# Urukul_FPGA.net
KiCad netlist of a schematic drawn in Altium Designer
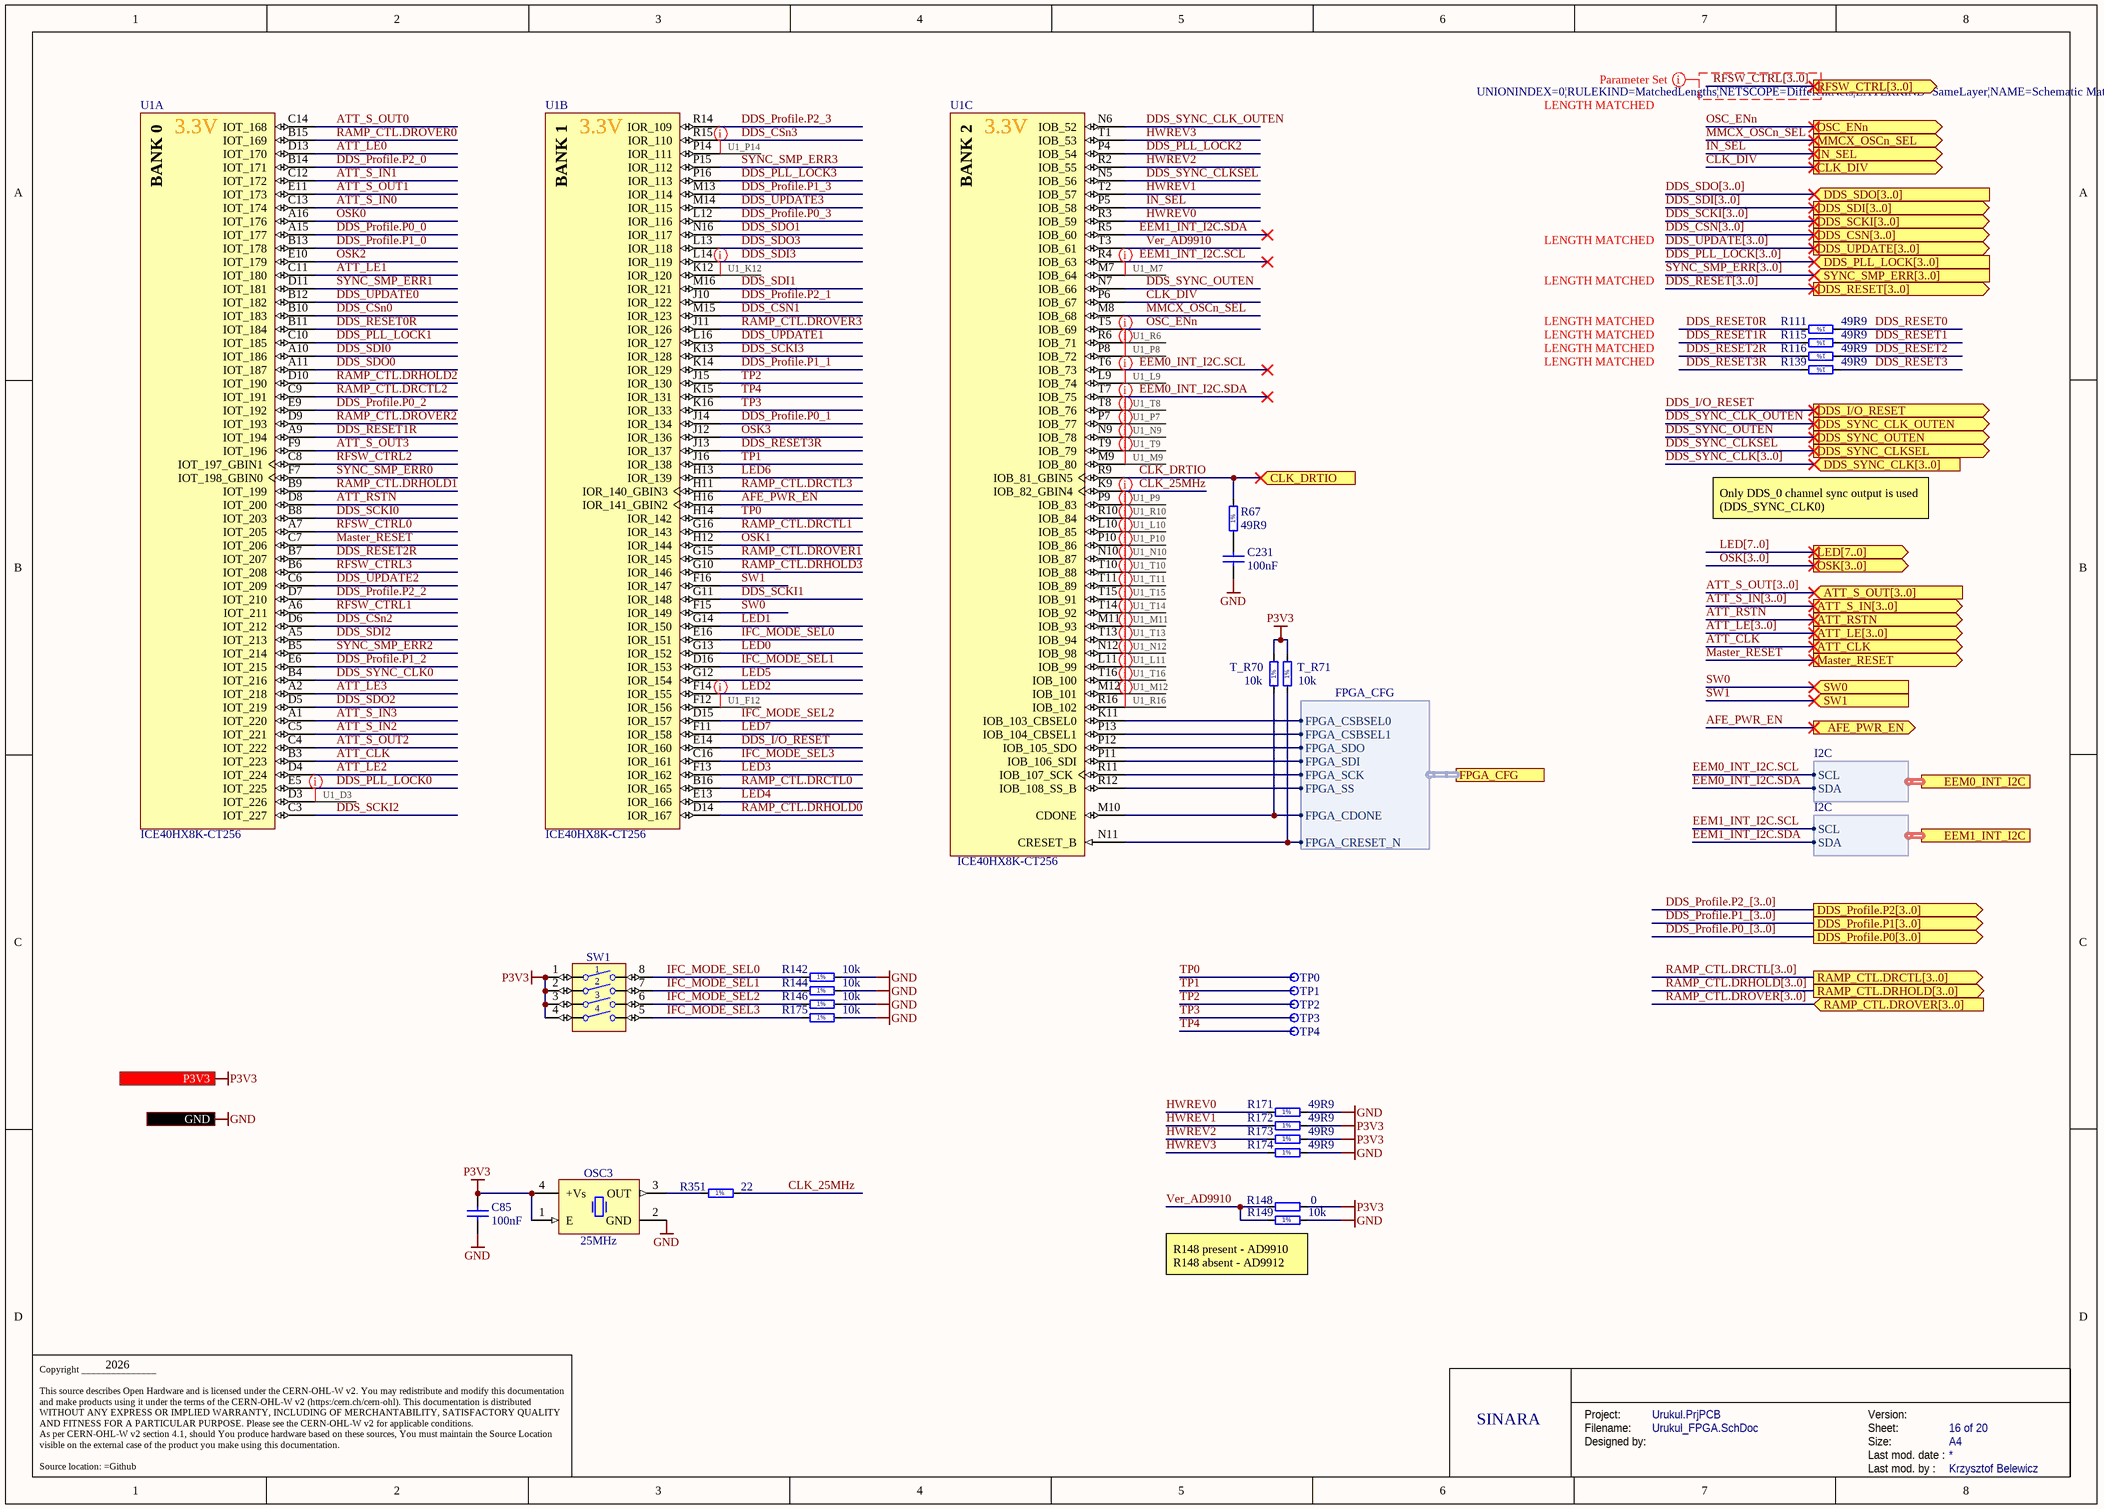
[diagram p0: Urukul_FPGA.SchDoc]

(export (version "E")
  (design (tool "Eeschema 10.0.6"))
  (components
    (comp (ref "C85")
      (value "100nF")
      (footprint "CAPC1005X55N")
      (description "Non-polarised capacitor")
      (fields
        (field (name "PART NUMBER") "CC0402_100NF_16V_10%_X5R")
        (field (name "VOLTAGE") "16V")
        (field (name "AUTHOR") "CERN DEM JLC")
      )
      (libsource (lib "Capacitors") (part "Capacitor - non polarized"))
    )
    (comp (ref "C231")
      (value "100nF")
      (footprint "CAPC1005X55N")
      (description "Non-polarised capacitor")
      (fields
        (field (name "PART NUMBER") "CC0402_100NF_16V_10%_X5R")
        (field (name "VOLTAGE") "16V")
        (field (name "AUTHOR") "CERN DEM JLC")
      )
      (libsource (lib "Capacitors") (part "Capacitor - non polarized"))
    )
    (comp (ref "OSC3")
      (value "25MHz")
      (footprint "OSC_IQD_CFPS-39")
      (description "Oscillator 4 pins 1=E 2=GND 3=OUT 4=+Vs")
      (fields
        (field (name "PART NUMBER") "OSC_25MHZ_IQD_LFSPXO025165")
        (field (name "MANUFACTURER") "IQD FREQUENCY PRODUCTS")
        (field (name "AUTHOR") "CERN DEM JLC")
      )
      (libsource (lib "ICs And Semiconductors") (part "Oscillator 1E 2GND 3OUT 4Vs"))
    )
    (comp (ref "R67")
      (value "49R9")
      (footprint "RESC1005X40N")
      (description "Resistor - 1%")
      (fields
        (field (name "PART NUMBER") "R0402_49R9_1%_0.0625W_100PPM")
        (field (name "POWER") "0.0625W")
        (field (name "AUTHOR") "CERN DEM JLC")
      )
      (libsource (lib "Resistors") (part "Resistor - 1%"))
    )
    (comp (ref "R111")
      (value "49R9")
      (footprint "RESC1005X40N")
      (description "Resistor - 1%")
      (fields
        (field (name "PART NUMBER") "R0402_49R9_1%_0.0625W_100PPM")
        (field (name "POWER") "0.0625W")
        (field (name "AUTHOR") "CERN DEM JLC")
      )
      (libsource (lib "Resistors") (part "Resistor - 1%"))
    )
    (comp (ref "R115")
      (value "49R9")
      (footprint "RESC1005X40N")
      (description "Resistor - 1%")
      (fields
        (field (name "PART NUMBER") "R0402_49R9_1%_0.0625W_100PPM")
        (field (name "POWER") "0.0625W")
        (field (name "AUTHOR") "CERN DEM JLC")
      )
      (libsource (lib "Resistors") (part "Resistor - 1%"))
    )
    (comp (ref "R116")
      (value "49R9")
      (footprint "RESC1005X40N")
      (description "Resistor - 1%")
      (fields
        (field (name "PART NUMBER") "R0402_49R9_1%_0.0625W_100PPM")
        (field (name "POWER") "0.0625W")
        (field (name "AUTHOR") "CERN DEM JLC")
      )
      (libsource (lib "Resistors") (part "Resistor - 1%"))
    )
    (comp (ref "R139")
      (value "49R9")
      (footprint "RESC1005X40N")
      (description "Resistor - 1%")
      (fields
        (field (name "PART NUMBER") "R0402_49R9_1%_0.0625W_100PPM")
        (field (name "POWER") "0.0625W")
        (field (name "AUTHOR") "CERN DEM JLC")
      )
      (libsource (lib "Resistors") (part "Resistor - 1%"))
    )
    (comp (ref "R142")
      (value "10k")
      (footprint "RESC1005X40N")
      (description "Resistor - 1%")
      (fields
        (field (name "PART NUMBER") "R0402_10K_1%_0.0625W_100PPM")
        (field (name "POWER") "0.0625W")
        (field (name "AUTHOR") "CERN DEM JLC")
      )
      (libsource (lib "Resistors") (part "Resistor - 1%"))
    )
    (comp (ref "R144")
      (value "10k")
      (footprint "RESC1005X40N")
      (description "Resistor - 1%")
      (fields
        (field (name "PART NUMBER") "R0402_10K_1%_0.0625W_100PPM")
        (field (name "POWER") "0.0625W")
        (field (name "AUTHOR") "CERN DEM JLC")
      )
      (libsource (lib "Resistors") (part "Resistor - 1%"))
    )
    (comp (ref "R146")
      (value "10k")
      (footprint "RESC1005X40N")
      (description "Resistor - 1%")
      (fields
        (field (name "PART NUMBER") "R0402_10K_1%_0.0625W_100PPM")
        (field (name "POWER") "0.0625W")
        (field (name "AUTHOR") "CERN DEM JLC")
      )
      (libsource (lib "Resistors") (part "Resistor - 1%"))
    )
    (comp (ref "R148")
      (value "0")
      (footprint "RESC1005X40N")
      (description "Resistor")
      (fields
        (field (name "PART NUMBER") "R0402_0R_JUMPER")
        (field (name "MANUFACTURER") "GENERIC")
        (field (name "AUTHOR") "CERN DEM JLC")
      )
      (libsource (lib "Resistors") (part "Resistor"))
    )
    (comp (ref "R149")
      (value "10k")
      (footprint "RESC1005X40N")
      (description "Resistor - 1%")
      (fields
        (field (name "PART NUMBER") "R0402_10K_1%_0.0625W_100PPM")
        (field (name "POWER") "0.0625W")
        (field (name "AUTHOR") "CERN DEM JLC")
      )
      (libsource (lib "Resistors") (part "Resistor - 1%"))
    )
    (comp (ref "R171")
      (value "49R9")
      (footprint "RESC1005X40N")
      (description "Resistor - 1%")
      (fields
        (field (name "PART NUMBER") "R0402_49R9_1%_0.0625W_100PPM")
        (field (name "POWER") "0.0625W")
        (field (name "AUTHOR") "CERN DEM JLC")
      )
      (libsource (lib "Resistors") (part "Resistor - 1%"))
    )
    (comp (ref "R172")
      (value "49R9")
      (footprint "RESC1005X40N")
      (description "Resistor - 1%")
      (fields
        (field (name "PART NUMBER") "R0402_49R9_1%_0.0625W_100PPM")
        (field (name "POWER") "0.0625W")
        (field (name "AUTHOR") "CERN DEM JLC")
      )
      (libsource (lib "Resistors") (part "Resistor - 1%"))
    )
    (comp (ref "R173")
      (value "49R9")
      (footprint "RESC1005X40N")
      (description "Resistor - 1%")
      (fields
        (field (name "PART NUMBER") "R0402_49R9_1%_0.0625W_100PPM")
        (field (name "POWER") "0.0625W")
        (field (name "AUTHOR") "CERN DEM JLC")
      )
      (libsource (lib "Resistors") (part "Resistor - 1%"))
    )
    (comp (ref "R174")
      (value "49R9")
      (footprint "RESC1005X40N")
      (description "Resistor - 1%")
      (fields
        (field (name "PART NUMBER") "R0402_49R9_1%_0.0625W_100PPM")
        (field (name "POWER") "0.0625W")
        (field (name "AUTHOR") "CERN DEM JLC")
      )
      (libsource (lib "Resistors") (part "Resistor - 1%"))
    )
    (comp (ref "R175")
      (value "10k")
      (footprint "RESC1005X40N")
      (description "Resistor - 1%")
      (fields
        (field (name "PART NUMBER") "R0402_10K_1%_0.0625W_100PPM")
        (field (name "POWER") "0.0625W")
        (field (name "AUTHOR") "CERN DEM JLC")
      )
      (libsource (lib "Resistors") (part "Resistor - 1%"))
    )
    (comp (ref "R351")
      (value "22")
      (footprint "RESC1005X40N")
      (description "Resistor - 1%")
      (fields
        (field (name "PART NUMBER") "R0402_22R_1%_0.0625W_100PPM")
        (field (name "POWER") "0.0625W")
        (field (name "AUTHOR") "CERN DEM JLC")
      )
      (libsource (lib "Resistors") (part "Resistor - 1%"))
    )
    (comp (ref "SW1")
      (value "Switch")
      (footprint "SW_TYCO_1571983-4")
      (description "4 Ways SPST DIP Switch")
      (fields
        (field (name "PART NUMBER") "SW_TYCO_1571983-4")
        (field (name "MANUFACTURER") "TYCO")
        (field (name "AUTHOR") "CERN DEM JLC")
      )
      (libsource (lib "Eletro-mechanical") (part "SW 4x SPST DIP Switch"))
    )
    (comp (ref "TP0")
      (value "Test Point")
      (footprint "TPS127")
      (fields (field (name "PART NUMBER") "SMD_PAD_1.27X1.27MM") (field (name "AUTHOR") "CERN DEM JLC"))
      (libsource (lib "Eletro-mechanical") (part "Test Point"))
    )
    (comp (ref "TP1")
      (value "Test Point")
      (footprint "TPS127")
      (fields (field (name "PART NUMBER") "SMD_PAD_1.27X1.27MM") (field (name "AUTHOR") "CERN DEM JLC"))
      (libsource (lib "Eletro-mechanical") (part "Test Point"))
    )
    (comp (ref "TP2")
      (value "Test Point")
      (footprint "TPS127")
      (fields (field (name "PART NUMBER") "SMD_PAD_1.27X1.27MM") (field (name "AUTHOR") "CERN DEM JLC"))
      (libsource (lib "Eletro-mechanical") (part "Test Point"))
    )
    (comp (ref "TP3")
      (value "Test Point")
      (footprint "TPS127")
      (fields (field (name "PART NUMBER") "SMD_PAD_1.27X1.27MM") (field (name "AUTHOR") "CERN DEM JLC"))
      (libsource (lib "Eletro-mechanical") (part "Test Point"))
    )
    (comp (ref "TP4")
      (value "Test Point")
      (footprint "TPS127")
      (fields (field (name "PART NUMBER") "SMD_PAD_1.27X1.27MM") (field (name "AUTHOR") "CERN DEM JLC"))
      (libsource (lib "Eletro-mechanical") (part "Test Point"))
    )
    (comp (ref "T_R70")
      (value "10k")
      (footprint "RESC1005X40N")
      (description "Resistor - 1%")
      (fields
        (field (name "PART NUMBER") "R0402_10K_1%_0.0625W_100PPM")
        (field (name "POWER") "0.0625W")
        (field (name "AUTHOR") "CERN DEM JLC")
      )
      (libsource (lib "Resistors") (part "Resistor - 1%"))
    )
    (comp (ref "T_R71")
      (value "10k")
      (footprint "RESC1005X40N")
      (description "Resistor - 1%")
      (fields
        (field (name "PART NUMBER") "R0402_10K_1%_0.0625W_100PPM")
        (field (name "POWER") "0.0625W")
        (field (name "AUTHOR") "CERN DEM JLC")
      )
      (libsource (lib "Resistors") (part "Resistor - 1%"))
    )
    (comp (ref "U1")
      (value "ICE40HX8K-CT256")
      (footprint "LATC-caBGA-256")
      (fields (field (name "MANUFACTURER") "Lattice Semiconductor"))
      (libsource (lib "Altium Content Vault") (part "LATC-HX8K-caBGA-256"))
    )
  )
  (nets
    (net (code "9") (name "/AFE_PWR_EN") (class "Default")
      (node (ref "U1") (pin "H16") (pinfunction "IOR_141_GBIN2_H16") (pintype "bidirectional+no_connect"))
    )
    (net (code "10") (name "/ATT_CLK") (class "Default")
      (node (ref "U1") (pin "B3") (pinfunction "IOT_223_B3") (pintype "bidirectional+no_connect"))
    )
    (net (code "11") (name "/ATT_LE0") (class "Default")
      (node (ref "U1") (pin "D13") (pinfunction "IOT_170_D13") (pintype "bidirectional"))
    )
    (net (code "12") (name "/ATT_LE1") (class "Default")
      (node (ref "U1") (pin "C11") (pinfunction "IOT_180_C11") (pintype "bidirectional"))
    )
    (net (code "13") (name "/ATT_LE2") (class "Default")
      (node (ref "U1") (pin "D4") (pinfunction "IOT_224_D4") (pintype "bidirectional"))
    )
    (net (code "14") (name "/ATT_LE3") (class "Default")
      (node (ref "U1") (pin "A2") (pinfunction "IOT_218_A2") (pintype "bidirectional"))
    )
    (net (code "16") (name "/ATT_RSTN") (class "Default")
      (node (ref "U1") (pin "D8") (pinfunction "IOT_200_D8") (pintype "bidirectional+no_connect"))
    )
    (net (code "17") (name "/ATT_S_IN0") (class "Default")
      (node (ref "U1") (pin "C13") (pinfunction "IOT_174_C13") (pintype "bidirectional"))
    )
    (net (code "18") (name "/ATT_S_IN1") (class "Default")
      (node (ref "U1") (pin "C12") (pinfunction "IOT_172_C12") (pintype "bidirectional"))
    )
    (net (code "19") (name "/ATT_S_IN2") (class "Default")
      (node (ref "U1") (pin "C5") (pinfunction "IOT_221_C5") (pintype "bidirectional"))
    )
    (net (code "20") (name "/ATT_S_IN3") (class "Default")
      (node (ref "U1") (pin "A1") (pinfunction "IOT_220_A1") (pintype "bidirectional"))
    )
    (net (code "22") (name "/ATT_S_OUT0") (class "Default")
      (node (ref "U1") (pin "C14") (pinfunction "IOT_168_C14") (pintype "bidirectional"))
    )
    (net (code "23") (name "/ATT_S_OUT1") (class "Default")
      (node (ref "U1") (pin "E11") (pinfunction "IOT_173_E11") (pintype "bidirectional"))
    )
    (net (code "24") (name "/ATT_S_OUT2") (class "Default")
      (node (ref "U1") (pin "C4") (pinfunction "IOT_222_C4") (pintype "bidirectional"))
    )
    (net (code "25") (name "/ATT_S_OUT3") (class "Default")
      (node (ref "U1") (pin "F9") (pinfunction "IOT_196_F9") (pintype "bidirectional"))
    )
    (net (code "27") (name "/CLK_25MHz") (class "Default")
      (node (ref "R351") (pin "2") (pinfunction "2_2") (pintype "passive"))
      (node (ref "U1") (pin "K9") (pinfunction "IOB_82_GBIN4_K9") (pintype "bidirectional"))
    )
    (net (code "28") (name "/CLK_DIV") (class "Default")
      (node (ref "U1") (pin "P6") (pinfunction "IOB_67_P6") (pintype "bidirectional"))
    )
    (net (code "29") (name "/CLK_DRTIO") (class "Default")
      (node (ref "R67") (pin "2") (pinfunction "2_2") (pintype "passive"))
      (node (ref "U1") (pin "R9") (pinfunction "IOB_81_GBIN5_R9") (pintype "bidirectional"))
    )
    (net (code "30") (name "/DDS_CSN1") (class "Default")
      (node (ref "U1") (pin "M15") (pinfunction "IOR_123_M15") (pintype "bidirectional"))
    )
    (net (code "32") (name "/DDS_CSn0") (class "Default")
      (node (ref "U1") (pin "B10") (pinfunction "IOT_183_B10") (pintype "bidirectional"))
    )
    (net (code "33") (name "/DDS_CSn2") (class "Default")
      (node (ref "U1") (pin "D6") (pinfunction "IOT_212_D6") (pintype "bidirectional"))
    )
    (net (code "34") (name "/DDS_CSn3") (class "Default")
      (node (ref "U1") (pin "R15") (pinfunction "IOR_110_R15") (pintype "bidirectional"))
    )
    (net (code "35") (name "/DDS_I{slash}O_RESET") (class "Default")
      (node (ref "U1") (pin "E14") (pinfunction "IOR_160_E14") (pintype "bidirectional"))
    )
    (net (code "36") (name "/DDS_PLL_LOCK0") (class "Default")
      (node (ref "U1") (pin "E5") (pinfunction "IOT_225_E5") (pintype "bidirectional"))
    )
    (net (code "37") (name "/DDS_PLL_LOCK1") (class "Default")
      (node (ref "U1") (pin "C10") (pinfunction "IOT_185_C10") (pintype "bidirectional"))
    )
    (net (code "38") (name "/DDS_PLL_LOCK2") (class "Default")
      (node (ref "U1") (pin "P4") (pinfunction "IOB_54_P4") (pintype "bidirectional"))
    )
    (net (code "39") (name "/DDS_PLL_LOCK3") (class "Default")
      (node (ref "U1") (pin "P16") (pinfunction "IOR_113_P16") (pintype "bidirectional"))
    )
    (net (code "41") (name "/DDS_Profile.P0_0") (class "Default")
      (node (ref "U1") (pin "A15") (pinfunction "IOT_177_A15") (pintype "bidirectional"))
    )
    (net (code "42") (name "/DDS_Profile.P0_1") (class "Default")
      (node (ref "U1") (pin "J14") (pinfunction "IOR_134_J14") (pintype "bidirectional"))
    )
    (net (code "43") (name "/DDS_Profile.P0_2") (class "Default")
      (node (ref "U1") (pin "E9") (pinfunction "IOT_192_E9") (pintype "bidirectional"))
    )
    (net (code "44") (name "/DDS_Profile.P0_3") (class "Default")
      (node (ref "U1") (pin "L12") (pinfunction "IOR_116_L12") (pintype "bidirectional"))
    )
    (net (code "46") (name "/DDS_Profile.P1_0") (class "Default")
      (node (ref "U1") (pin "B13") (pinfunction "IOT_178_B13") (pintype "bidirectional"))
    )
    (net (code "47") (name "/DDS_Profile.P1_1") (class "Default")
      (node (ref "U1") (pin "K14") (pinfunction "IOR_129_K14") (pintype "bidirectional"))
    )
    (net (code "48") (name "/DDS_Profile.P1_2") (class "Default")
      (node (ref "U1") (pin "E6") (pinfunction "IOT_215_E6") (pintype "bidirectional"))
    )
    (net (code "49") (name "/DDS_Profile.P1_3") (class "Default")
      (node (ref "U1") (pin "M13") (pinfunction "IOR_114_M13") (pintype "bidirectional"))
    )
    (net (code "51") (name "/DDS_Profile.P2_0") (class "Default")
      (node (ref "U1") (pin "B14") (pinfunction "IOT_171_B14") (pintype "bidirectional"))
    )
    (net (code "52") (name "/DDS_Profile.P2_1") (class "Default")
      (node (ref "U1") (pin "J10") (pinfunction "IOR_122_J10") (pintype "bidirectional"))
    )
    (net (code "53") (name "/DDS_Profile.P2_2") (class "Default")
      (node (ref "U1") (pin "D7") (pinfunction "IOT_210_D7") (pintype "bidirectional"))
    )
    (net (code "54") (name "/DDS_Profile.P2_3") (class "Default")
      (node (ref "U1") (pin "R14") (pinfunction "IOR_109_R14") (pintype "bidirectional"))
    )
    (net (code "56") (name "/DDS_RESET0") (class "Default")
      (node (ref "R111") (pin "1") (pinfunction "1_1") (pintype "passive"))
    )
    (net (code "57") (name "/DDS_RESET0R") (class "Default")
      (node (ref "R111") (pin "2") (pinfunction "2_2") (pintype "passive"))
      (node (ref "U1") (pin "B11") (pinfunction "IOT_184_B11") (pintype "bidirectional"))
    )
    (net (code "58") (name "/DDS_RESET1") (class "Default")
      (node (ref "R115") (pin "1") (pinfunction "1_1") (pintype "passive"))
    )
    (net (code "59") (name "/DDS_RESET1R") (class "Default")
      (node (ref "R115") (pin "2") (pinfunction "2_2") (pintype "passive"))
      (node (ref "U1") (pin "A9") (pinfunction "IOT_194_A9") (pintype "bidirectional"))
    )
    (net (code "60") (name "/DDS_RESET2") (class "Default")
      (node (ref "R116") (pin "1") (pinfunction "1_1") (pintype "passive"))
    )
    (net (code "61") (name "/DDS_RESET2R") (class "Default")
      (node (ref "R116") (pin "2") (pinfunction "2_2") (pintype "passive"))
      (node (ref "U1") (pin "B7") (pinfunction "IOT_207_B7") (pintype "bidirectional"))
    )
    (net (code "62") (name "/DDS_RESET3") (class "Default")
      (node (ref "R139") (pin "1") (pinfunction "1_1") (pintype "passive"))
    )
    (net (code "63") (name "/DDS_RESET3R") (class "Default")
      (node (ref "R139") (pin "2") (pinfunction "2_2") (pintype "passive"))
      (node (ref "U1") (pin "J13") (pinfunction "IOR_137_J13") (pintype "bidirectional"))
    )
    (net (code "65") (name "/DDS_SCKI0") (class "Default")
      (node (ref "U1") (pin "B8") (pinfunction "IOT_203_B8") (pintype "bidirectional"))
    )
    (net (code "66") (name "/DDS_SCKI1") (class "Default")
      (node (ref "U1") (pin "G11") (pinfunction "IOR_148_G11") (pintype "bidirectional"))
    )
    (net (code "67") (name "/DDS_SCKI2") (class "Default")
      (node (ref "U1") (pin "C3") (pinfunction "IOT_227_C3") (pintype "bidirectional"))
    )
    (net (code "68") (name "/DDS_SCKI3") (class "Default")
      (node (ref "U1") (pin "K13") (pinfunction "IOR_128_K13") (pintype "bidirectional"))
    )
    (net (code "70") (name "/DDS_SDI0") (class "Default")
      (node (ref "U1") (pin "A10") (pinfunction "IOT_186_A10") (pintype "bidirectional"))
    )
    (net (code "71") (name "/DDS_SDI1") (class "Default")
      (node (ref "U1") (pin "M16") (pinfunction "IOR_121_M16") (pintype "bidirectional"))
    )
    (net (code "72") (name "/DDS_SDI2") (class "Default")
      (node (ref "U1") (pin "A5") (pinfunction "IOT_213_A5") (pintype "bidirectional"))
    )
    (net (code "73") (name "/DDS_SDI3") (class "Default")
      (node (ref "U1") (pin "L14") (pinfunction "IOR_119_L14") (pintype "bidirectional"))
    )
    (net (code "75") (name "/DDS_SDO0") (class "Default")
      (node (ref "U1") (pin "A11") (pinfunction "IOT_187_A11") (pintype "bidirectional"))
    )
    (net (code "76") (name "/DDS_SDO1") (class "Default")
      (node (ref "U1") (pin "N16") (pinfunction "IOR_117_N16") (pintype "bidirectional"))
    )
    (net (code "77") (name "/DDS_SDO2") (class "Default")
      (node (ref "U1") (pin "D5") (pinfunction "IOT_219_D5") (pintype "bidirectional"))
    )
    (net (code "78") (name "/DDS_SDO3") (class "Default")
      (node (ref "U1") (pin "L13") (pinfunction "IOR_118_L13") (pintype "bidirectional"))
    )
    (net (code "80") (name "/DDS_SYNC_CLK0") (class "Default")
      (node (ref "U1") (pin "B4") (pinfunction "IOT_216_B4") (pintype "bidirectional"))
    )
    (net (code "81") (name "/DDS_SYNC_CLKSEL") (class "Default")
      (node (ref "U1") (pin "N5") (pinfunction "IOB_56_N5") (pintype "bidirectional"))
    )
    (net (code "83") (name "/DDS_SYNC_CLK_OUTEN") (class "Default")
      (node (ref "U1") (pin "N6") (pinfunction "IOB_52_N6") (pintype "bidirectional"))
    )
    (net (code "84") (name "/DDS_SYNC_OUTEN") (class "Default")
      (node (ref "U1") (pin "N7") (pinfunction "IOB_66_N7") (pintype "bidirectional"))
    )
    (net (code "85") (name "/DDS_UPDATE0") (class "Default")
      (node (ref "U1") (pin "B12") (pinfunction "IOT_182_B12") (pintype "bidirectional"))
    )
    (net (code "86") (name "/DDS_UPDATE1") (class "Default")
      (node (ref "U1") (pin "L16") (pinfunction "IOR_127_L16") (pintype "bidirectional"))
    )
    (net (code "87") (name "/DDS_UPDATE2") (class "Default")
      (node (ref "U1") (pin "C6") (pinfunction "IOT_209_C6") (pintype "bidirectional"))
    )
    (net (code "88") (name "/DDS_UPDATE3") (class "Default")
      (node (ref "U1") (pin "M14") (pinfunction "IOR_115_M14") (pintype "bidirectional"))
    )
    (net (code "90") (name "/EEM0_INT_I2C.SCL") (class "Default")
      (node (ref "U1") (pin "T6") (pinfunction "IOB_73_T6") (pintype "bidirectional"))
    )
    (net (code "91") (name "/EEM0_INT_I2C.SDA") (class "Default")
      (node (ref "U1") (pin "T7") (pinfunction "IOB_75_T7") (pintype "bidirectional"))
    )
    (net (code "92") (name "/EEM1_INT_I2C.SCL") (class "Default")
      (node (ref "U1") (pin "R4") (pinfunction "IOB_63_R4") (pintype "bidirectional"))
    )
    (net (code "93") (name "/EEM1_INT_I2C.SDA") (class "Default")
      (node (ref "U1") (pin "R5") (pinfunction "IOB_60_R5") (pintype "bidirectional"))
    )
    (net (code "94") (name "/FPGA_CDONE") (class "Default")
      (node (ref "T_R70") (pin "1") (pinfunction "1_1") (pintype "passive"))
      (node (ref "U1") (pin "M10") (pinfunction "CDONE_M10") (pintype "bidirectional"))
    )
    (net (code "95") (name "/FPGA_CRESET_N") (class "Default")
      (node (ref "T_R71") (pin "1") (pinfunction "1_1") (pintype "passive"))
      (node (ref "U1") (pin "N11") (pinfunction "CRESET_B_N11") (pintype "input"))
    )
    (net (code "96") (name "/FPGA_CSBSEL0") (class "Default")
      (node (ref "U1") (pin "K11") (pinfunction "IOB_103_CBSEL0_K11") (pintype "bidirectional"))
    )
    (net (code "97") (name "/FPGA_CSBSEL1") (class "Default")
      (node (ref "U1") (pin "P13") (pinfunction "IOB_104_CBSEL1_P13") (pintype "bidirectional"))
    )
    (net (code "98") (name "/FPGA_SCK") (class "Default")
      (node (ref "U1") (pin "R11") (pinfunction "IOB_107_SCK_R11") (pintype "bidirectional"))
    )
    (net (code "99") (name "/FPGA_SDI") (class "Default")
      (node (ref "U1") (pin "P11") (pinfunction "IOB_106_SDI_P11") (pintype "bidirectional"))
    )
    (net (code "100") (name "/FPGA_SDO") (class "Default")
      (node (ref "U1") (pin "P12") (pinfunction "IOB_105_SDO_P12") (pintype "bidirectional"))
    )
    (net (code "101") (name "/FPGA_SS") (class "Default")
      (node (ref "U1") (pin "R12") (pinfunction "IOB_108_SS_B_R12") (pintype "bidirectional"))
    )
    (net (code "102") (name "/HWREV0") (class "Default")
      (node (ref "R171") (pin "2") (pinfunction "2_2") (pintype "passive"))
      (node (ref "U1") (pin "R3") (pinfunction "IOB_59_R3") (pintype "bidirectional"))
    )
    (net (code "103") (name "/HWREV1") (class "Default")
      (node (ref "R172") (pin "2") (pinfunction "2_2") (pintype "passive"))
      (node (ref "U1") (pin "T2") (pinfunction "IOB_57_T2") (pintype "bidirectional"))
    )
    (net (code "104") (name "/HWREV2") (class "Default")
      (node (ref "R173") (pin "2") (pinfunction "2_2") (pintype "passive"))
      (node (ref "U1") (pin "R2") (pinfunction "IOB_55_R2") (pintype "bidirectional"))
    )
    (net (code "105") (name "/HWREV3") (class "Default")
      (node (ref "R174") (pin "2") (pinfunction "2_2") (pintype "passive"))
      (node (ref "U1") (pin "T1") (pinfunction "IOB_53_T1") (pintype "bidirectional"))
    )
    (net (code "106") (name "/IFC_MODE_SEL0") (class "Default")
      (node (ref "R142") (pin "2") (pinfunction "2_2") (pintype "passive"))
      (node (ref "SW1") (pin "8") (pinfunction "8_8") (pintype "bidirectional"))
      (node (ref "U1") (pin "E16") (pinfunction "IOR_151_E16") (pintype "bidirectional"))
    )
    (net (code "107") (name "/IFC_MODE_SEL1") (class "Default")
      (node (ref "R144") (pin "2") (pinfunction "2_2") (pintype "passive"))
      (node (ref "SW1") (pin "7") (pinfunction "7_7") (pintype "bidirectional"))
      (node (ref "U1") (pin "D16") (pinfunction "IOR_153_D16") (pintype "bidirectional"))
    )
    (net (code "108") (name "/IFC_MODE_SEL2") (class "Default")
      (node (ref "R146") (pin "2") (pinfunction "2_2") (pintype "passive"))
      (node (ref "SW1") (pin "6") (pinfunction "6_6") (pintype "bidirectional"))
      (node (ref "U1") (pin "D15") (pinfunction "IOR_157_D15") (pintype "bidirectional"))
    )
    (net (code "109") (name "/IFC_MODE_SEL3") (class "Default")
      (node (ref "R175") (pin "2") (pinfunction "2_2") (pintype "passive"))
      (node (ref "SW1") (pin "5") (pinfunction "5_5") (pintype "bidirectional"))
      (node (ref "U1") (pin "C16") (pinfunction "IOR_161_C16") (pintype "bidirectional"))
    )
    (net (code "110") (name "/IN_SEL") (class "Default")
      (node (ref "U1") (pin "P5") (pinfunction "IOB_58_P5") (pintype "bidirectional"))
    )
    (net (code "111") (name "/LED0") (class "Default")
      (node (ref "U1") (pin "G13") (pinfunction "IOR_152_G13") (pintype "bidirectional"))
    )
    (net (code "112") (name "/LED1") (class "Default")
      (node (ref "U1") (pin "G14") (pinfunction "IOR_150_G14") (pintype "bidirectional"))
    )
    (net (code "113") (name "/LED2") (class "Default")
      (node (ref "U1") (pin "F14") (pinfunction "IOR_155_F14") (pintype "bidirectional"))
    )
    (net (code "114") (name "/LED3") (class "Default")
      (node (ref "U1") (pin "F13") (pinfunction "IOR_162_F13") (pintype "bidirectional"))
    )
    (net (code "115") (name "/LED4") (class "Default")
      (node (ref "U1") (pin "E13") (pinfunction "IOR_166_E13") (pintype "bidirectional"))
    )
    (net (code "116") (name "/LED5") (class "Default")
      (node (ref "U1") (pin "G12") (pinfunction "IOR_154_G12") (pintype "bidirectional"))
    )
    (net (code "117") (name "/LED6") (class "Default")
      (node (ref "U1") (pin "H13") (pinfunction "IOR_139_H13") (pintype "bidirectional"))
    )
    (net (code "118") (name "/LED7") (class "Default")
      (node (ref "U1") (pin "F11") (pinfunction "IOR_158_F11") (pintype "bidirectional"))
    )
    (net (code "120") (name "/MMCX_OSCn_SEL") (class "Default")
      (node (ref "U1") (pin "M8") (pinfunction "IOB_68_M8") (pintype "bidirectional"))
    )
    (net (code "121") (name "/Master_RESET") (class "Default")
      (node (ref "U1") (pin "C7") (pinfunction "IOT_206_C7") (pintype "bidirectional+no_connect"))
    )
    (net (code "122") (name "/OSC_ENn") (class "Default")
      (node (ref "U1") (pin "T5") (pinfunction "IOB_69_T5") (pintype "bidirectional"))
    )
    (net (code "123") (name "/OSK0") (class "Default")
      (node (ref "U1") (pin "A16") (pinfunction "IOT_176_A16") (pintype "bidirectional"))
    )
    (net (code "124") (name "/OSK1") (class "Default")
      (node (ref "U1") (pin "H12") (pinfunction "IOR_144_H12") (pintype "bidirectional"))
    )
    (net (code "125") (name "/OSK2") (class "Default")
      (node (ref "U1") (pin "E10") (pinfunction "IOT_179_E10") (pintype "bidirectional"))
    )
    (net (code "126") (name "/OSK3") (class "Default")
      (node (ref "U1") (pin "J12") (pinfunction "IOR_136_J12") (pintype "bidirectional"))
    )
    (net (code "128") (name "/RAMP_CTL.DRCTL0") (class "Default")
      (node (ref "U1") (pin "B16") (pinfunction "IOR_165_B16") (pintype "bidirectional"))
    )
    (net (code "129") (name "/RAMP_CTL.DRCTL1") (class "Default")
      (node (ref "U1") (pin "G16") (pinfunction "IOR_143_G16") (pintype "bidirectional"))
    )
    (net (code "130") (name "/RAMP_CTL.DRCTL2") (class "Default")
      (node (ref "U1") (pin "C9") (pinfunction "IOT_191_C9") (pintype "bidirectional"))
    )
    (net (code "131") (name "/RAMP_CTL.DRCTL3") (class "Default")
      (node (ref "U1") (pin "H11") (pinfunction "IOR_140_GBIN3_H11") (pintype "bidirectional"))
    )
    (net (code "133") (name "/RAMP_CTL.DRHOLD0") (class "Default")
      (node (ref "U1") (pin "D14") (pinfunction "IOR_167_D14") (pintype "bidirectional"))
    )
    (net (code "134") (name "/RAMP_CTL.DRHOLD1") (class "Default")
      (node (ref "U1") (pin "B9") (pinfunction "IOT_199_B9") (pintype "bidirectional"))
    )
    (net (code "135") (name "/RAMP_CTL.DRHOLD2") (class "Default")
      (node (ref "U1") (pin "D10") (pinfunction "IOT_190_D10") (pintype "bidirectional"))
    )
    (net (code "136") (name "/RAMP_CTL.DRHOLD3") (class "Default")
      (node (ref "U1") (pin "G10") (pinfunction "IOR_146_G10") (pintype "bidirectional"))
    )
    (net (code "138") (name "/RAMP_CTL.DROVER0") (class "Default")
      (node (ref "U1") (pin "B15") (pinfunction "IOT_169_B15") (pintype "bidirectional"))
    )
    (net (code "139") (name "/RAMP_CTL.DROVER1") (class "Default")
      (node (ref "U1") (pin "G15") (pinfunction "IOR_145_G15") (pintype "bidirectional"))
    )
    (net (code "140") (name "/RAMP_CTL.DROVER2") (class "Default")
      (node (ref "U1") (pin "D9") (pinfunction "IOT_193_D9") (pintype "bidirectional"))
    )
    (net (code "141") (name "/RAMP_CTL.DROVER3") (class "Default")
      (node (ref "U1") (pin "J11") (pinfunction "IOR_126_J11") (pintype "bidirectional"))
    )
    (net (code "143") (name "/RFSW_CTRL0") (class "Default")
      (node (ref "U1") (pin "A7") (pinfunction "IOT_205_A7") (pintype "bidirectional"))
    )
    (net (code "144") (name "/RFSW_CTRL1") (class "Default")
      (node (ref "U1") (pin "A6") (pinfunction "IOT_211_A6") (pintype "bidirectional"))
    )
    (net (code "145") (name "/RFSW_CTRL2") (class "Default")
      (node (ref "U1") (pin "C8") (pinfunction "IOT_197_GBIN1_C8") (pintype "bidirectional"))
    )
    (net (code "146") (name "/RFSW_CTRL3") (class "Default")
      (node (ref "U1") (pin "B6") (pinfunction "IOT_208_B6") (pintype "bidirectional"))
    )
    (net (code "148") (name "/SW0") (class "Default")
      (node (ref "U1") (pin "F15") (pinfunction "IOR_149_F15") (pintype "bidirectional+no_connect"))
    )
    (net (code "149") (name "/SW1") (class "Default")
      (node (ref "U1") (pin "F16") (pinfunction "IOR_147_F16") (pintype "bidirectional+no_connect"))
    )
    (net (code "150") (name "/SYNC_SMP_ERR0") (class "Default")
      (node (ref "U1") (pin "F7") (pinfunction "IOT_198_GBIN0_F7") (pintype "bidirectional"))
    )
    (net (code "151") (name "/SYNC_SMP_ERR1") (class "Default")
      (node (ref "U1") (pin "D11") (pinfunction "IOT_181_D11") (pintype "bidirectional"))
    )
    (net (code "152") (name "/SYNC_SMP_ERR2") (class "Default")
      (node (ref "U1") (pin "B5") (pinfunction "IOT_214_B5") (pintype "bidirectional"))
    )
    (net (code "153") (name "/SYNC_SMP_ERR3") (class "Default")
      (node (ref "U1") (pin "P15") (pinfunction "IOR_112_P15") (pintype "bidirectional"))
    )
    (net (code "155") (name "/TP0") (class "Default")
      (node (ref "TP0") (pin "1") (pinfunction "1_1") (pintype "bidirectional"))
      (node (ref "U1") (pin "H14") (pinfunction "IOR_142_H14") (pintype "bidirectional"))
    )
    (net (code "156") (name "/TP1") (class "Default")
      (node (ref "TP1") (pin "1") (pinfunction "1_1") (pintype "bidirectional"))
      (node (ref "U1") (pin "J16") (pinfunction "IOR_138_J16") (pintype "bidirectional"))
    )
    (net (code "157") (name "/TP2") (class "Default")
      (node (ref "TP2") (pin "1") (pinfunction "1_1") (pintype "bidirectional"))
      (node (ref "U1") (pin "J15") (pinfunction "IOR_130_J15") (pintype "bidirectional"))
    )
    (net (code "158") (name "/TP3") (class "Default")
      (node (ref "TP3") (pin "1") (pinfunction "1_1") (pintype "bidirectional"))
      (node (ref "U1") (pin "K16") (pinfunction "IOR_133_K16") (pintype "bidirectional"))
    )
    (net (code "159") (name "/TP4") (class "Default")
      (node (ref "TP4") (pin "1") (pinfunction "1_1") (pintype "bidirectional"))
      (node (ref "U1") (pin "K15") (pinfunction "IOR_131_K15") (pintype "bidirectional"))
    )
    (net (code "160") (name "/U1_D3") (class "Default")
      (node (ref "U1") (pin "D3") (pinfunction "IOT_226_D3") (pintype "bidirectional"))
    )
    (net (code "161") (name "/U1_F12") (class "Default")
      (node (ref "U1") (pin "F12") (pinfunction "IOR_156_F12") (pintype "bidirectional"))
    )
    (net (code "162") (name "/U1_K12") (class "Default")
      (node (ref "U1") (pin "K12") (pinfunction "IOR_120_K12") (pintype "bidirectional"))
    )
    (net (code "163") (name "/U1_L9") (class "Default")
      (node (ref "U1") (pin "L9") (pinfunction "IOB_74_L9") (pintype "bidirectional"))
    )
    (net (code "164") (name "/U1_L10") (class "Default")
      (node (ref "U1") (pin "L10") (pinfunction "IOB_85_L10") (pintype "bidirectional"))
    )
    (net (code "165") (name "/U1_L11") (class "Default")
      (node (ref "U1") (pin "L11") (pinfunction "IOB_99_L11") (pintype "bidirectional"))
    )
    (net (code "166") (name "/U1_M7") (class "Default")
      (node (ref "U1") (pin "M7") (pinfunction "IOB_64_M7") (pintype "bidirectional"))
    )
    (net (code "167") (name "/U1_M9") (class "Default")
      (node (ref "U1") (pin "M9") (pinfunction "IOB_80_M9") (pintype "bidirectional"))
    )
    (net (code "168") (name "/U1_M11") (class "Default")
      (node (ref "U1") (pin "M11") (pinfunction "IOB_93_M11") (pintype "bidirectional"))
    )
    (net (code "169") (name "/U1_M12") (class "Default")
      (node (ref "U1") (pin "M12") (pinfunction "IOB_101_M12") (pintype "bidirectional"))
    )
    (net (code "170") (name "/U1_N9") (class "Default")
      (node (ref "U1") (pin "N9") (pinfunction "IOB_78_N9") (pintype "bidirectional"))
    )
    (net (code "171") (name "/U1_N10") (class "Default")
      (node (ref "U1") (pin "N10") (pinfunction "IOB_87_N10") (pintype "bidirectional"))
    )
    (net (code "172") (name "/U1_N12") (class "Default")
      (node (ref "U1") (pin "N12") (pinfunction "IOB_98_N12") (pintype "bidirectional"))
    )
    (net (code "173") (name "/U1_P7") (class "Default")
      (node (ref "U1") (pin "P7") (pinfunction "IOB_77_P7") (pintype "bidirectional"))
    )
    (net (code "174") (name "/U1_P8") (class "Default")
      (node (ref "U1") (pin "P8") (pinfunction "IOB_72_P8") (pintype "bidirectional"))
    )
    (net (code "175") (name "/U1_P9") (class "Default")
      (node (ref "U1") (pin "P9") (pinfunction "IOB_83_P9") (pintype "bidirectional"))
    )
    (net (code "176") (name "/U1_P10") (class "Default")
      (node (ref "U1") (pin "P10") (pinfunction "IOB_86_P10") (pintype "bidirectional"))
    )
    (net (code "177") (name "/U1_P14") (class "Default")
      (node (ref "U1") (pin "P14") (pinfunction "IOR_111_P14") (pintype "bidirectional"))
    )
    (net (code "178") (name "/U1_R6") (class "Default")
      (node (ref "U1") (pin "R6") (pinfunction "IOB_71_R6") (pintype "bidirectional"))
    )
    (net (code "179") (name "/U1_R10") (class "Default")
      (node (ref "U1") (pin "R10") (pinfunction "IOB_84_R10") (pintype "bidirectional"))
    )
    (net (code "180") (name "/U1_R16") (class "Default")
      (node (ref "U1") (pin "R16") (pinfunction "IOB_102_R16") (pintype "bidirectional"))
    )
    (net (code "181") (name "/U1_T8") (class "Default")
      (node (ref "U1") (pin "T8") (pinfunction "IOB_76_T8") (pintype "bidirectional"))
    )
    (net (code "182") (name "/U1_T9") (class "Default")
      (node (ref "U1") (pin "T9") (pinfunction "IOB_79_T9") (pintype "bidirectional"))
    )
    (net (code "183") (name "/U1_T10") (class "Default")
      (node (ref "U1") (pin "T10") (pinfunction "IOB_88_T10") (pintype "bidirectional"))
    )
    (net (code "184") (name "/U1_T11") (class "Default")
      (node (ref "U1") (pin "T11") (pinfunction "IOB_89_T11") (pintype "bidirectional"))
    )
    (net (code "185") (name "/U1_T13") (class "Default")
      (node (ref "U1") (pin "T13") (pinfunction "IOB_94_T13") (pintype "bidirectional"))
    )
    (net (code "186") (name "/U1_T14") (class "Default")
      (node (ref "U1") (pin "T14") (pinfunction "IOB_92_T14") (pintype "bidirectional"))
    )
    (net (code "187") (name "/U1_T15") (class "Default")
      (node (ref "U1") (pin "T15") (pinfunction "IOB_91_T15") (pintype "bidirectional"))
    )
    (net (code "188") (name "/U1_T16") (class "Default")
      (node (ref "U1") (pin "T16") (pinfunction "IOB_100_T16") (pintype "bidirectional"))
    )
    (net (code "189") (name "/Ver_AD9910") (class "Default")
      (node (ref "R148") (pin "1") (pinfunction "1_1") (pintype "passive"))
      (node (ref "R149") (pin "2") (pinfunction "2_2") (pintype "passive"))
      (node (ref "U1") (pin "T3") (pinfunction "IOB_61_T3") (pintype "bidirectional"))
    )
    (net (code "192") (name "GND") (class "Default")
      (node (ref "C231") (pin "1") (pinfunction "1_1") (pintype "passive"))
      (node (ref "C85") (pin "1") (pinfunction "1_1") (pintype "passive"))
      (node (ref "OSC3") (pin "2") (pinfunction "GND_2") (pintype "power_in"))
      (node (ref "R142") (pin "1") (pinfunction "1_1") (pintype "passive"))
      (node (ref "R144") (pin "1") (pinfunction "1_1") (pintype "passive"))
      (node (ref "R146") (pin "1") (pinfunction "1_1") (pintype "passive"))
      (node (ref "R149") (pin "1") (pinfunction "1_1") (pintype "passive"))
      (node (ref "R171") (pin "1") (pinfunction "1_1") (pintype "passive"))
      (node (ref "R174") (pin "1") (pinfunction "1_1") (pintype "passive"))
      (node (ref "R175") (pin "1") (pinfunction "1_1") (pintype "passive"))
    )
    (net (code "193") (name "Net-(C231-Pad2)") (class "Default")
      (node (ref "C231") (pin "2") (pinfunction "2_2") (pintype "passive"))
      (node (ref "R67") (pin "1") (pinfunction "1_1") (pintype "passive"))
    )
    (net (code "194") (name "Net-(OSC3-OUT)") (class "Default")
      (node (ref "OSC3") (pin "3") (pinfunction "OUT_3") (pintype "output"))
      (node (ref "R351") (pin "1") (pinfunction "1_1") (pintype "passive"))
    )
    (net (code "195") (name "P3V3") (class "Default")
      (node (ref "C85") (pin "2") (pinfunction "2_2") (pintype "passive"))
      (node (ref "OSC3") (pin "1") (pinfunction "E_1") (pintype "input"))
      (node (ref "OSC3") (pin "4") (pinfunction "+Vs_4") (pintype "power_in"))
      (node (ref "R148") (pin "2") (pinfunction "2_2") (pintype "passive"))
      (node (ref "R172") (pin "1") (pinfunction "1_1") (pintype "passive"))
      (node (ref "R173") (pin "1") (pinfunction "1_1") (pintype "passive"))
      (node (ref "SW1") (pin "1") (pinfunction "1_1") (pintype "bidirectional"))
      (node (ref "SW1") (pin "2") (pinfunction "2_2") (pintype "bidirectional"))
      (node (ref "SW1") (pin "3") (pinfunction "3_3") (pintype "bidirectional"))
      (node (ref "SW1") (pin "4") (pinfunction "4_4") (pintype "bidirectional"))
      (node (ref "T_R70") (pin "2") (pinfunction "2_2") (pintype "passive"))
      (node (ref "T_R71") (pin "2") (pinfunction "2_2") (pintype "passive"))
    )
  )
)
